# PPGv2.net
KiCad netlist of a schematic drawn in EAGLE
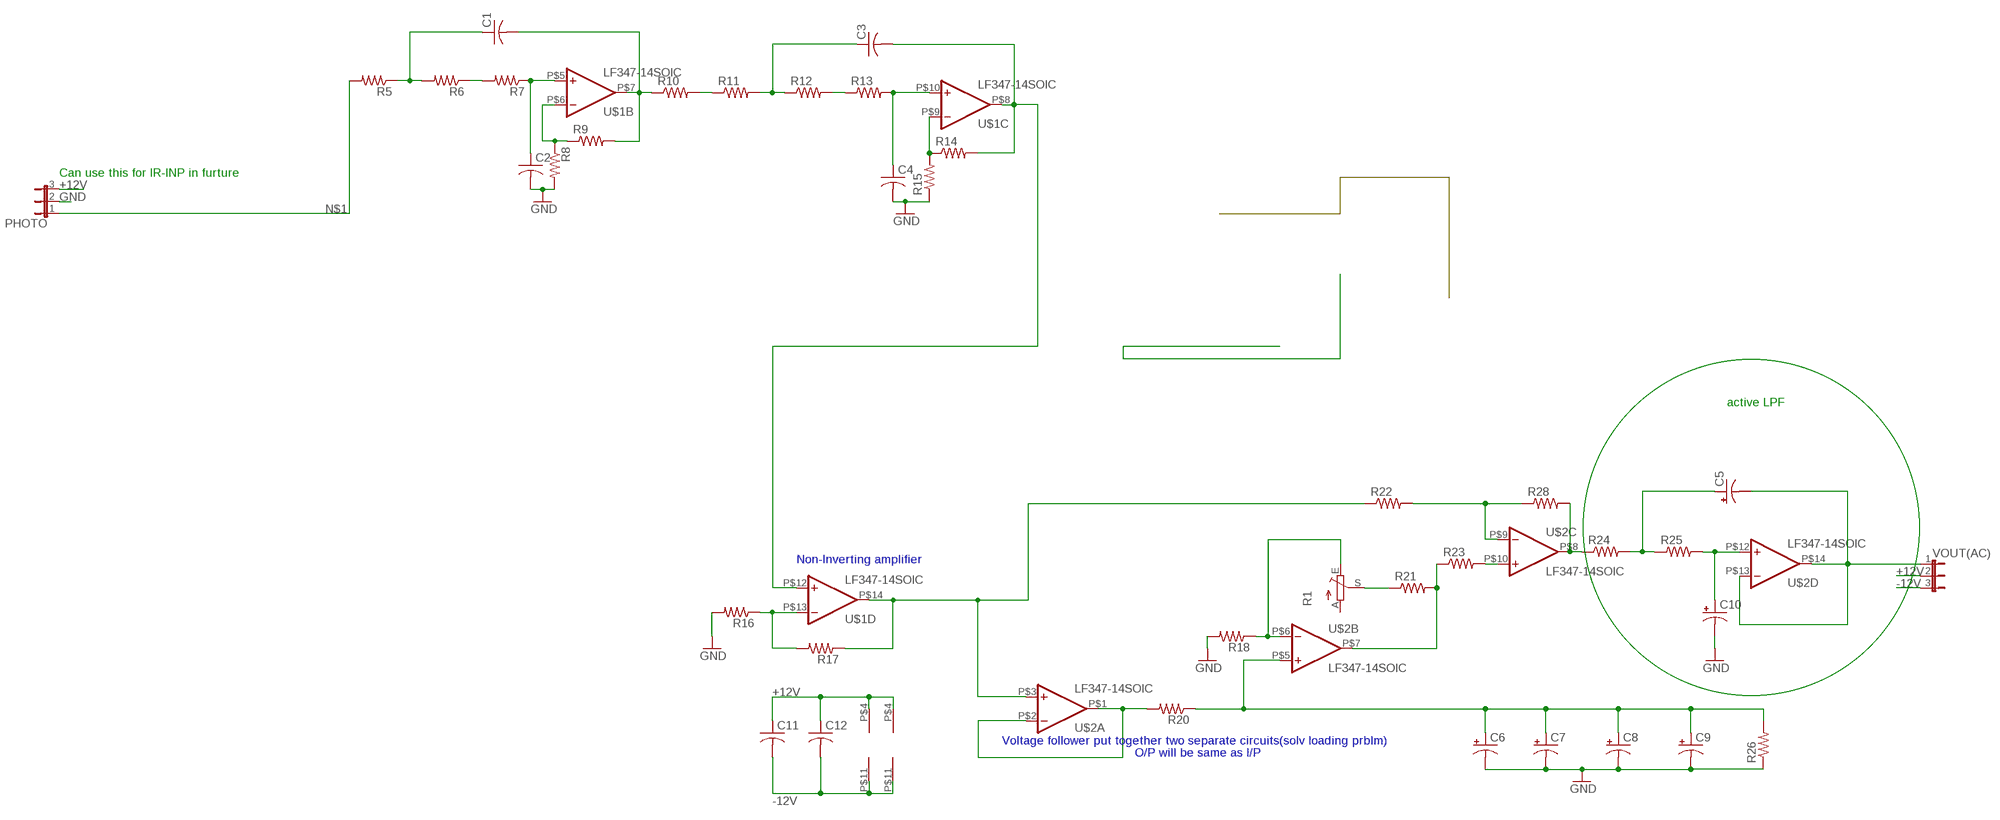
[diagram p0: schematic, sheet 1]

(export (version "E")
  (design (tool "Eeschema 10.0.6"))
  (components
    (comp (ref "C1")
      (value "CAP0603")
      (footprint "eagle-import:C0603")
      (libsource (lib "eagle-import") (part "CAP0603"))
    )
    (comp (ref "C2")
      (value "CAP0603")
      (footprint "eagle-import:C0603")
      (libsource (lib "eagle-import") (part "CAP0603"))
    )
    (comp (ref "C3")
      (value "CAP0603")
      (footprint "eagle-import:C0603")
      (libsource (lib "eagle-import") (part "CAP0603"))
    )
    (comp (ref "C4")
      (value "CAP0603")
      (footprint "eagle-import:C0603")
      (libsource (lib "eagle-import") (part "CAP0603"))
    )
    (comp (ref "C5")
      (value "CAP_POL_10V")
      (footprint "eagle-import:C_6032-28R")
      (libsource (lib "eagle-import") (part "CAP_POL_10V"))
    )
    (comp (ref "C6")
      (value "CAP_POL_10V")
      (footprint "eagle-import:C_6032-28R")
      (libsource (lib "eagle-import") (part "CAP_POL_10V"))
    )
    (comp (ref "C7")
      (value "CAP_POL_10V")
      (footprint "eagle-import:C_6032-28R")
      (libsource (lib "eagle-import") (part "CAP_POL_10V"))
    )
    (comp (ref "C8")
      (value "CAP_POL_10V")
      (footprint "eagle-import:C_6032-28R")
      (libsource (lib "eagle-import") (part "CAP_POL_10V"))
    )
    (comp (ref "C9")
      (value "CAP_POL_10V")
      (footprint "eagle-import:C_6032-28R")
      (libsource (lib "eagle-import") (part "CAP_POL_10V"))
    )
    (comp (ref "C10")
      (value "CAP_POL_10V")
      (footprint "eagle-import:C_6032-28R")
      (libsource (lib "eagle-import") (part "CAP_POL_10V"))
    )
    (comp (ref "C11")
      (value "CAP0603")
      (footprint "eagle-import:C0603")
      (libsource (lib "eagle-import") (part "CAP0603"))
    )
    (comp (ref "C12")
      (value "CAP0603")
      (footprint "eagle-import:C0603")
      (libsource (lib "eagle-import") (part "CAP0603"))
    )
    (comp (ref "PHOTO")
      (value "JP2E")
      (footprint "eagle-import:JP2")
      (libsource (lib "eagle-import") (part "JP2E"))
    )
    (comp (ref "R1")
      (value "TRIM_EU-RJ9W")
      (footprint "eagle-import:RJ9W")
      (libsource (lib "eagle-import") (part "TRIM_EU-RJ9W"))
    )
    (comp (ref "R5")
      (value "R-US_R0603")
      (footprint "eagle-import:R0603")
      (libsource (lib "eagle-import") (part "R-US_R0603"))
    )
    (comp (ref "R6")
      (value "R-US_R0603")
      (footprint "eagle-import:R0603")
      (libsource (lib "eagle-import") (part "R-US_R0603"))
    )
    (comp (ref "R7")
      (value "R-US_R0603")
      (footprint "eagle-import:R0603")
      (libsource (lib "eagle-import") (part "R-US_R0603"))
    )
    (comp (ref "R8")
      (value "R-US_R0603")
      (footprint "eagle-import:R0603")
      (libsource (lib "eagle-import") (part "R-US_R0603"))
    )
    (comp (ref "R9")
      (value "R-US_R0603")
      (footprint "eagle-import:R0603")
      (libsource (lib "eagle-import") (part "R-US_R0603"))
    )
    (comp (ref "R10")
      (value "R-US_R0603")
      (footprint "eagle-import:R0603")
      (libsource (lib "eagle-import") (part "R-US_R0603"))
    )
    (comp (ref "R11")
      (value "R-US_R0603")
      (footprint "eagle-import:R0603")
      (libsource (lib "eagle-import") (part "R-US_R0603"))
    )
    (comp (ref "R12")
      (value "R-US_R0603")
      (footprint "eagle-import:R0603")
      (libsource (lib "eagle-import") (part "R-US_R0603"))
    )
    (comp (ref "R13")
      (value "R-US_R0603")
      (footprint "eagle-import:R0603")
      (libsource (lib "eagle-import") (part "R-US_R0603"))
    )
    (comp (ref "R14")
      (value "R-US_R0603")
      (footprint "eagle-import:R0603")
      (libsource (lib "eagle-import") (part "R-US_R0603"))
    )
    (comp (ref "R15")
      (value "R-US_R0603")
      (footprint "eagle-import:R0603")
      (libsource (lib "eagle-import") (part "R-US_R0603"))
    )
    (comp (ref "R16")
      (value "R-US_R0603")
      (footprint "eagle-import:R0603")
      (libsource (lib "eagle-import") (part "R-US_R0603"))
    )
    (comp (ref "R17")
      (value "R-US_R0603")
      (footprint "eagle-import:R0603")
      (libsource (lib "eagle-import") (part "R-US_R0603"))
    )
    (comp (ref "R18")
      (value "R-US_R0603")
      (footprint "eagle-import:R0603")
      (libsource (lib "eagle-import") (part "R-US_R0603"))
    )
    (comp (ref "R20")
      (value "R-US_R0603")
      (footprint "eagle-import:R0603")
      (libsource (lib "eagle-import") (part "R-US_R0603"))
    )
    (comp (ref "R21")
      (value "R-US_R0603")
      (footprint "eagle-import:R0603")
      (libsource (lib "eagle-import") (part "R-US_R0603"))
    )
    (comp (ref "R22")
      (value "R-US_R0603")
      (footprint "eagle-import:R0603")
      (libsource (lib "eagle-import") (part "R-US_R0603"))
    )
    (comp (ref "R23")
      (value "R-US_R0603")
      (footprint "eagle-import:R0603")
      (libsource (lib "eagle-import") (part "R-US_R0603"))
    )
    (comp (ref "R24")
      (value "R-US_R0603")
      (footprint "eagle-import:R0603")
      (libsource (lib "eagle-import") (part "R-US_R0603"))
    )
    (comp (ref "R25")
      (value "R-US_R0603")
      (footprint "eagle-import:R0603")
      (libsource (lib "eagle-import") (part "R-US_R0603"))
    )
    (comp (ref "R26")
      (value "R-US_R0603")
      (footprint "eagle-import:R0603")
      (libsource (lib "eagle-import") (part "R-US_R0603"))
    )
    (comp (ref "R28")
      (value "R-US_R0603")
      (footprint "eagle-import:R0603")
      (libsource (lib "eagle-import") (part "R-US_R0603"))
    )
    (comp (ref "U$1")
      (value "LF347-14SOIC")
      (footprint "eagle-import:SOIC14")
      (libsource (lib "eagle-import") (part "LF347-14SOIC"))
    )
    (comp (ref "U$2")
      (value "LF347-14SOIC")
      (footprint "eagle-import:SOIC14")
      (libsource (lib "eagle-import") (part "LF347-14SOIC"))
    )
    (comp (ref "VOUT(AC)")
      (value "JP2E")
      (footprint "eagle-import:JP2")
      (libsource (lib "eagle-import") (part "JP2E"))
    )
  )
  (nets
    (net (code "1") (name "/+12V") (class "Default")
      (node (ref "C11") (pin "1") (pinfunction "1_1") (pintype "passive"))
      (node (ref "C12") (pin "1") (pinfunction "1_1") (pintype "passive"))
      (node (ref "PHOTO") (pin "3") (pinfunction "3_3") (pintype "passive"))
      (node (ref "U$1") (pin "P$4") (pinfunction "VCC_P$4") (pintype "power_in"))
      (node (ref "U$2") (pin "P$4") (pinfunction "VCC_P$4") (pintype "power_in"))
      (node (ref "VOUT(AC)") (pin "2") (pinfunction "2_2") (pintype "passive"))
    )
    (net (code "2") (name "/-12V") (class "Default")
      (node (ref "C11") (pin "2") (pinfunction "2_2") (pintype "passive"))
      (node (ref "C12") (pin "2") (pinfunction "2_2") (pintype "passive"))
      (node (ref "U$1") (pin "P$11") (pinfunction "VEE_P$11") (pintype "power_in"))
      (node (ref "U$2") (pin "P$11") (pinfunction "VEE_P$11") (pintype "power_in"))
      (node (ref "VOUT(AC)") (pin "3") (pinfunction "3_3") (pintype "passive"))
    )
    (net (code "3") (name "/N$1") (class "Default")
      (node (ref "PHOTO") (pin "1") (pinfunction "1_1") (pintype "passive"))
      (node (ref "R5") (pin "2") (pinfunction "2_2") (pintype "passive"))
    )
    (net (code "4") (name "GND") (class "Default")
      (node (ref "C10") (pin "-") (pinfunction "-_-") (pintype "passive"))
      (node (ref "C2") (pin "2") (pinfunction "2_2") (pintype "passive"))
      (node (ref "C4") (pin "2") (pinfunction "2_2") (pintype "passive"))
      (node (ref "C6") (pin "-") (pinfunction "-_-") (pintype "passive"))
      (node (ref "C7") (pin "-") (pinfunction "-_-") (pintype "passive"))
      (node (ref "C8") (pin "-") (pinfunction "-_-") (pintype "passive"))
      (node (ref "C9") (pin "-") (pinfunction "-_-") (pintype "passive"))
      (node (ref "PHOTO") (pin "2") (pinfunction "2_2") (pintype "passive"))
      (node (ref "R15") (pin "1") (pinfunction "1_1") (pintype "passive"))
      (node (ref "R16") (pin "2") (pinfunction "2_2") (pintype "passive"))
      (node (ref "R18") (pin "2") (pinfunction "2_2") (pintype "passive"))
      (node (ref "R26") (pin "1") (pinfunction "1_1") (pintype "passive"))
      (node (ref "R8") (pin "2") (pinfunction "2_2") (pintype "passive"))
    )
    (net (code "5") (name "Net-(C1-Pad1)") (class "Default")
      (node (ref "C1") (pin "1") (pinfunction "1_1") (pintype "passive"))
      (node (ref "R5") (pin "1") (pinfunction "1_1") (pintype "passive"))
      (node (ref "R6") (pin "2") (pinfunction "2_2") (pintype "passive"))
    )
    (net (code "6") (name "Net-(C3-Pad1)") (class "Default")
      (node (ref "C3") (pin "1") (pinfunction "1_1") (pintype "passive"))
      (node (ref "R11") (pin "2") (pinfunction "2_2") (pintype "passive"))
      (node (ref "R12") (pin "1") (pinfunction "1_1") (pintype "passive"))
    )
    (net (code "7") (name "Net-(C5-Pad+)") (class "Default")
      (node (ref "C5") (pin "+") (pinfunction "+_+") (pintype "passive"))
      (node (ref "R24") (pin "2") (pinfunction "2_2") (pintype "passive"))
      (node (ref "R25") (pin "1") (pinfunction "1_1") (pintype "passive"))
    )
    (net (code "8") (name "Net-(R1-PadS)") (class "Default")
      (node (ref "R1") (pin "S") (pinfunction "S_S") (pintype "passive"))
      (node (ref "R21") (pin "1") (pinfunction "1_1") (pintype "passive"))
    )
    (net (code "9") (name "Net-(R6-Pad1)") (class "Default")
      (node (ref "R6") (pin "1") (pinfunction "1_1") (pintype "passive"))
      (node (ref "R7") (pin "2") (pinfunction "2_2") (pintype "passive"))
    )
    (net (code "10") (name "Net-(R10-Pad2)") (class "Default")
      (node (ref "R10") (pin "2") (pinfunction "2_2") (pintype "passive"))
      (node (ref "R11") (pin "1") (pinfunction "1_1") (pintype "passive"))
    )
    (net (code "11") (name "Net-(R12-Pad2)") (class "Default")
      (node (ref "R12") (pin "2") (pinfunction "2_2") (pintype "passive"))
      (node (ref "R13") (pin "1") (pinfunction "1_1") (pintype "passive"))
    )
    (net (code "12") (name "Net-(U$1B-IN+)") (class "Default")
      (node (ref "C2") (pin "1") (pinfunction "1_1") (pintype "passive"))
      (node (ref "R7") (pin "1") (pinfunction "1_1") (pintype "passive"))
      (node (ref "U$1") (pin "P$5") (pinfunction "IN+_P$5") (pintype "input"))
    )
    (net (code "13") (name "Net-(U$1B-IN-)") (class "Default")
      (node (ref "R8") (pin "1") (pinfunction "1_1") (pintype "passive"))
      (node (ref "R9") (pin "1") (pinfunction "1_1") (pintype "passive"))
      (node (ref "U$1") (pin "P$6") (pinfunction "IN-_P$6") (pintype "input"))
    )
    (net (code "14") (name "Net-(U$1B-OUT)") (class "Default")
      (node (ref "C1") (pin "2") (pinfunction "2_2") (pintype "passive"))
      (node (ref "R10") (pin "1") (pinfunction "1_1") (pintype "passive"))
      (node (ref "R9") (pin "2") (pinfunction "2_2") (pintype "passive"))
      (node (ref "U$1") (pin "P$7") (pinfunction "OUT_P$7") (pintype "output"))
    )
    (net (code "15") (name "Net-(U$1C-IN+)") (class "Default")
      (node (ref "C4") (pin "1") (pinfunction "1_1") (pintype "passive"))
      (node (ref "R13") (pin "2") (pinfunction "2_2") (pintype "passive"))
      (node (ref "U$1") (pin "P$10") (pinfunction "IN+_P$10") (pintype "input"))
    )
    (net (code "16") (name "Net-(U$1C-IN-)") (class "Default")
      (node (ref "R14") (pin "1") (pinfunction "1_1") (pintype "passive"))
      (node (ref "R15") (pin "2") (pinfunction "2_2") (pintype "passive"))
      (node (ref "U$1") (pin "P$9") (pinfunction "IN-_P$9") (pintype "input"))
    )
    (net (code "17") (name "Net-(U$1C-OUT)") (class "Default")
      (node (ref "C3") (pin "2") (pinfunction "2_2") (pintype "passive"))
      (node (ref "R14") (pin "2") (pinfunction "2_2") (pintype "passive"))
      (node (ref "U$1") (pin "P$12") (pinfunction "IN+_P$12") (pintype "input"))
      (node (ref "U$1") (pin "P$8") (pinfunction "OUT_P$8") (pintype "output"))
    )
    (net (code "18") (name "Net-(U$1D-IN-)") (class "Default")
      (node (ref "R16") (pin "1") (pinfunction "1_1") (pintype "passive"))
      (node (ref "R17") (pin "2") (pinfunction "2_2") (pintype "passive"))
      (node (ref "U$1") (pin "P$13") (pinfunction "IN-_P$13") (pintype "input"))
    )
    (net (code "19") (name "Net-(U$1D-OUT)") (class "Default")
      (node (ref "R17") (pin "1") (pinfunction "1_1") (pintype "passive"))
      (node (ref "R22") (pin "1") (pinfunction "1_1") (pintype "passive"))
      (node (ref "U$1") (pin "P$14") (pinfunction "OUT_P$14") (pintype "output"))
      (node (ref "U$2") (pin "P$3") (pinfunction "IN+_P$3") (pintype "input"))
    )
    (net (code "20") (name "Net-(U$2A-IN-)") (class "Default")
      (node (ref "R20") (pin "2") (pinfunction "2_2") (pintype "passive"))
      (node (ref "U$2") (pin "P$1") (pinfunction "OUT_P$1") (pintype "output"))
      (node (ref "U$2") (pin "P$2") (pinfunction "IN-_P$2") (pintype "input"))
    )
    (net (code "21") (name "Net-(U$2B-IN+)") (class "Default")
      (node (ref "C6") (pin "+") (pinfunction "+_+") (pintype "passive"))
      (node (ref "C7") (pin "+") (pinfunction "+_+") (pintype "passive"))
      (node (ref "C8") (pin "+") (pinfunction "+_+") (pintype "passive"))
      (node (ref "C9") (pin "+") (pinfunction "+_+") (pintype "passive"))
      (node (ref "R20") (pin "1") (pinfunction "1_1") (pintype "passive"))
      (node (ref "R26") (pin "2") (pinfunction "2_2") (pintype "passive"))
      (node (ref "U$2") (pin "P$5") (pinfunction "IN+_P$5") (pintype "input"))
    )
    (net (code "22") (name "Net-(U$2B-IN-)") (class "Default")
      (node (ref "R1") (pin "E") (pinfunction "E_E") (pintype "passive"))
      (node (ref "R18") (pin "1") (pinfunction "1_1") (pintype "passive"))
      (node (ref "U$2") (pin "P$6") (pinfunction "IN-_P$6") (pintype "input"))
    )
    (net (code "23") (name "Net-(U$2B-OUT)") (class "Default")
      (node (ref "R21") (pin "2") (pinfunction "2_2") (pintype "passive"))
      (node (ref "R23") (pin "1") (pinfunction "1_1") (pintype "passive"))
      (node (ref "U$2") (pin "P$7") (pinfunction "OUT_P$7") (pintype "output"))
    )
    (net (code "24") (name "Net-(U$2C-IN+)") (class "Default")
      (node (ref "R23") (pin "2") (pinfunction "2_2") (pintype "passive"))
      (node (ref "U$2") (pin "P$10") (pinfunction "IN+_P$10") (pintype "input"))
    )
    (net (code "25") (name "Net-(U$2C-IN-)") (class "Default")
      (node (ref "R22") (pin "2") (pinfunction "2_2") (pintype "passive"))
      (node (ref "R28") (pin "1") (pinfunction "1_1") (pintype "passive"))
      (node (ref "U$2") (pin "P$9") (pinfunction "IN-_P$9") (pintype "input"))
    )
    (net (code "26") (name "Net-(U$2C-OUT)") (class "Default")
      (node (ref "R24") (pin "1") (pinfunction "1_1") (pintype "passive"))
      (node (ref "R28") (pin "2") (pinfunction "2_2") (pintype "passive"))
      (node (ref "U$2") (pin "P$8") (pinfunction "OUT_P$8") (pintype "output"))
    )
    (net (code "27") (name "Net-(U$2D-IN+)") (class "Default")
      (node (ref "C10") (pin "+") (pinfunction "+_+") (pintype "passive"))
      (node (ref "R25") (pin "2") (pinfunction "2_2") (pintype "passive"))
      (node (ref "U$2") (pin "P$12") (pinfunction "IN+_P$12") (pintype "input"))
    )
    (net (code "28") (name "Net-(U$2D-IN-)") (class "Default")
      (node (ref "C5") (pin "-") (pinfunction "-_-") (pintype "passive"))
      (node (ref "U$2") (pin "P$13") (pinfunction "IN-_P$13") (pintype "input"))
      (node (ref "U$2") (pin "P$14") (pinfunction "OUT_P$14") (pintype "output"))
      (node (ref "VOUT(AC)") (pin "1") (pinfunction "1_1") (pintype "passive"))
    )
    (net (code "29") (name "unconnected-(R1-PadA)") (class "Default")
      (node (ref "R1") (pin "A") (pinfunction "A_A") (pintype "passive"))
    )
  )
)
